# pcb.net
KiCad netlist of a schematic drawn in EAGLE
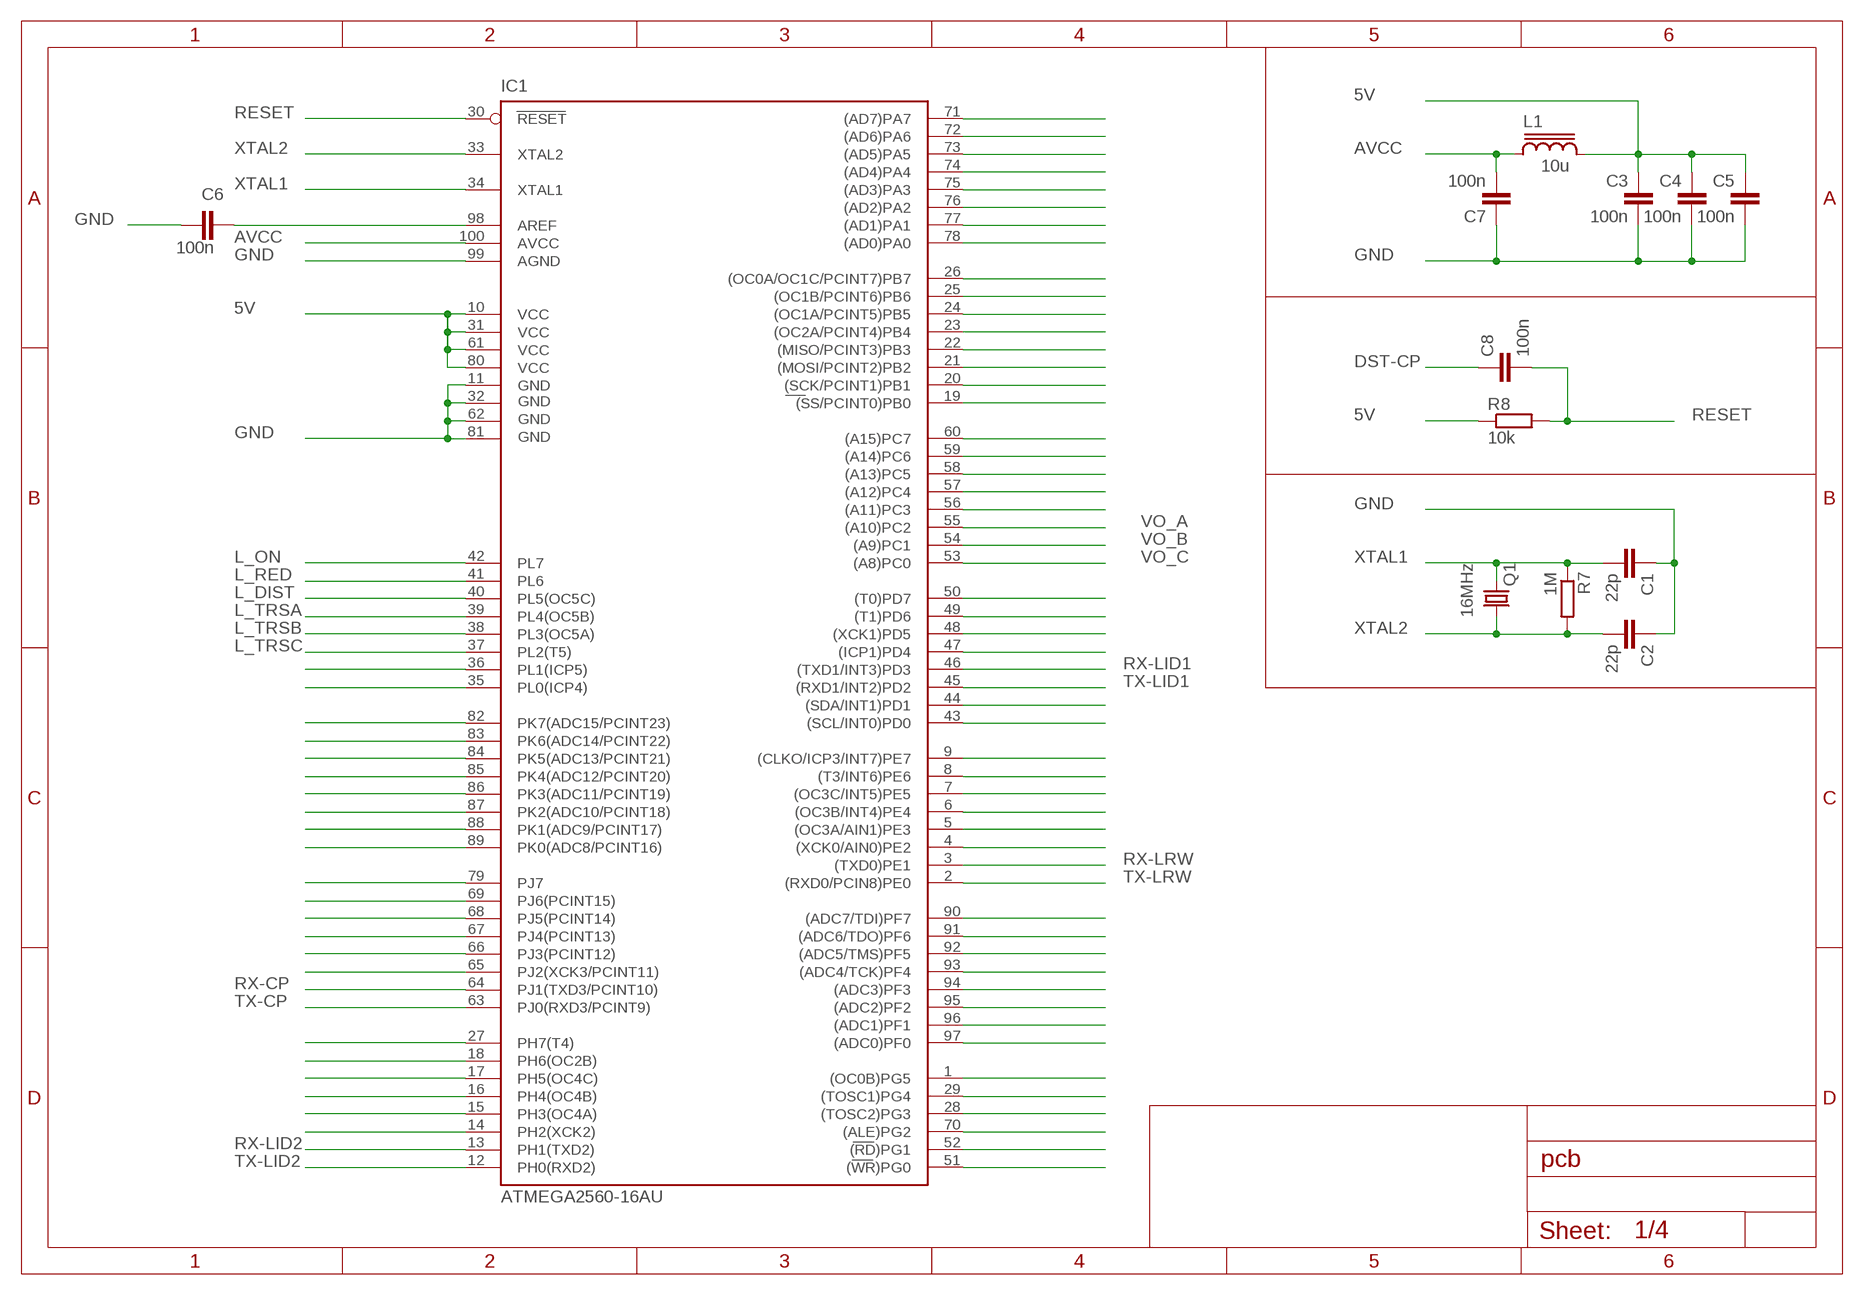
[diagram p0: schematic, sheet 1]
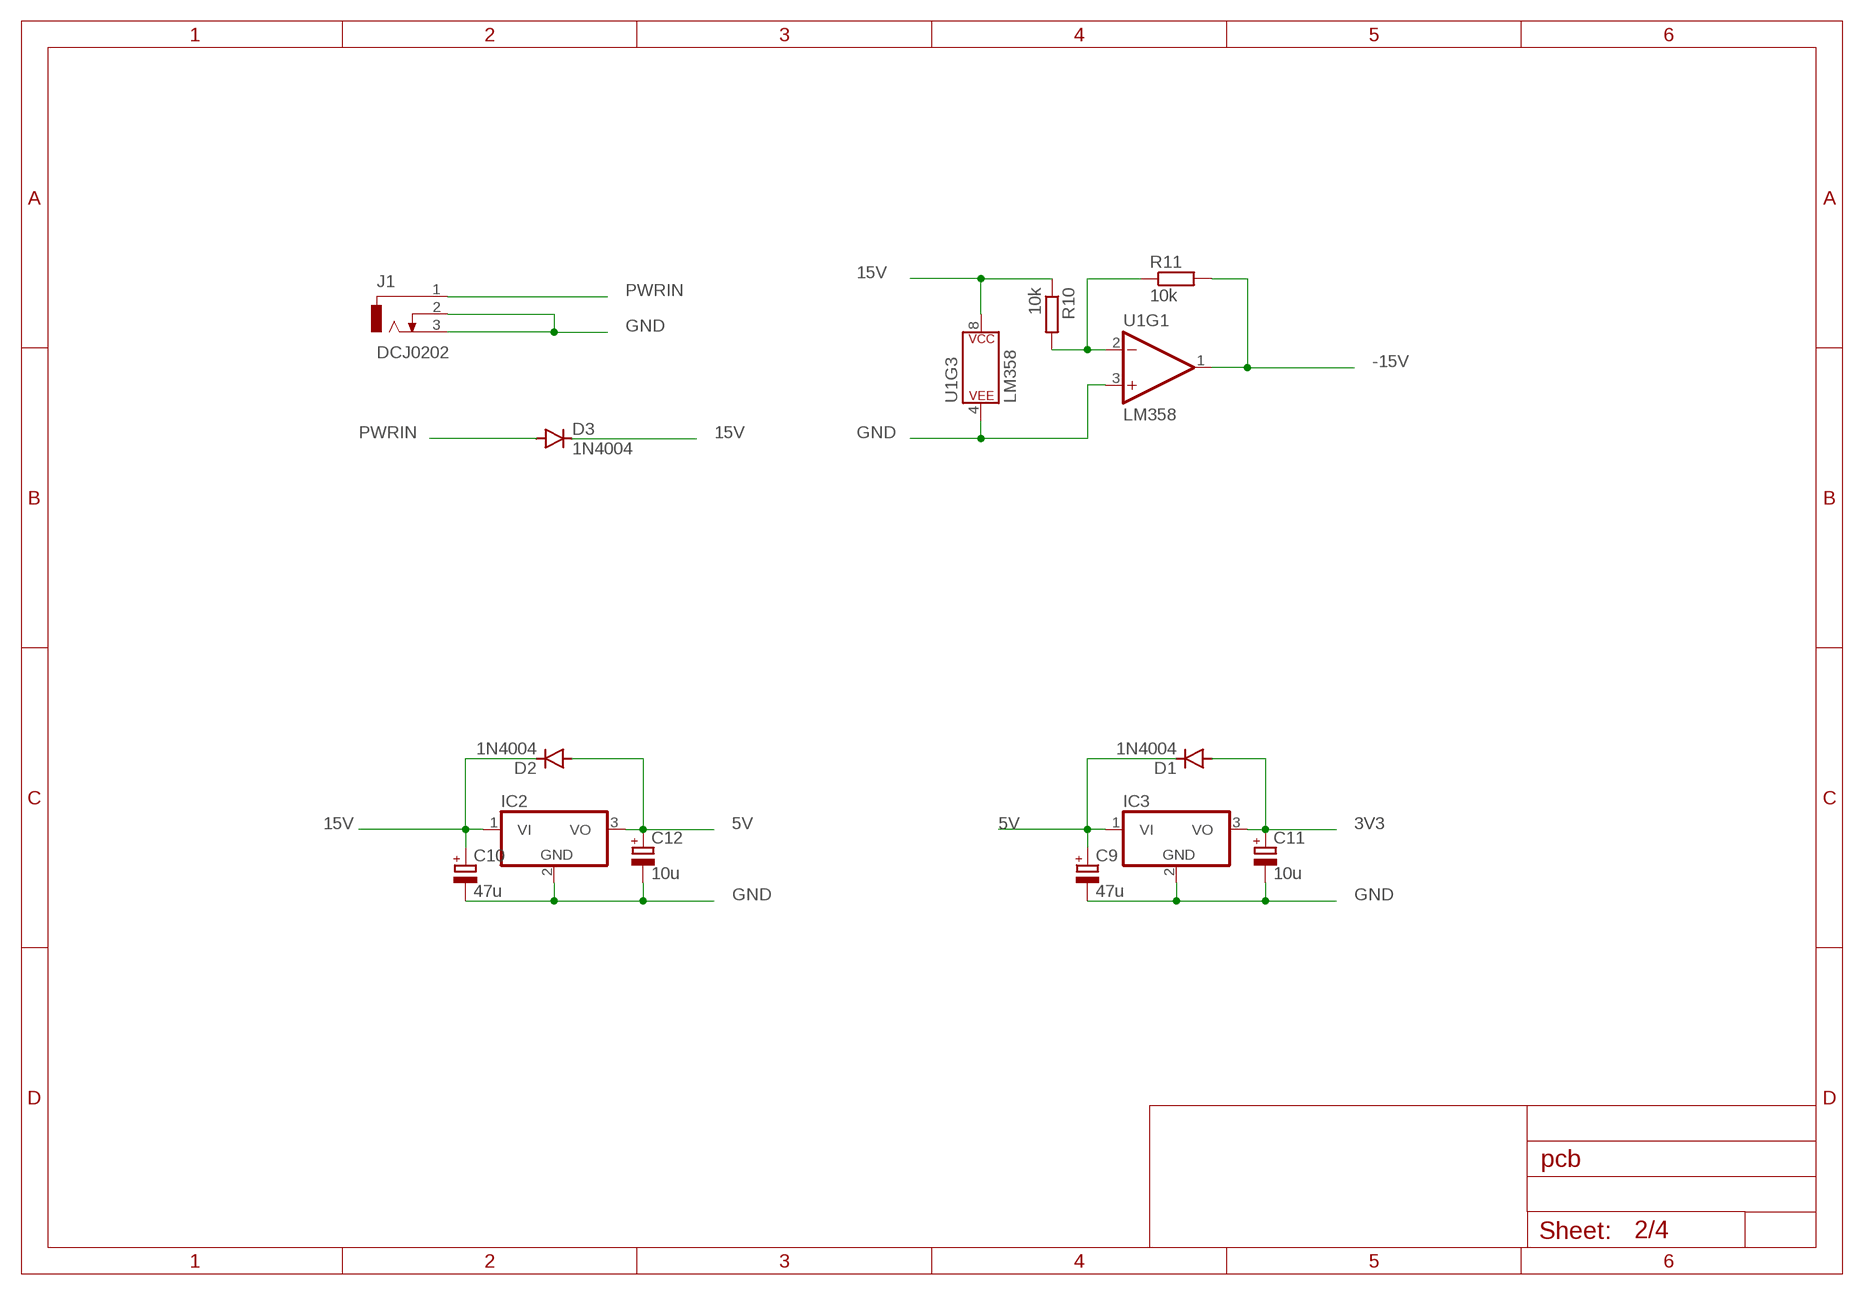
[diagram p1: schematic, sheet 2]
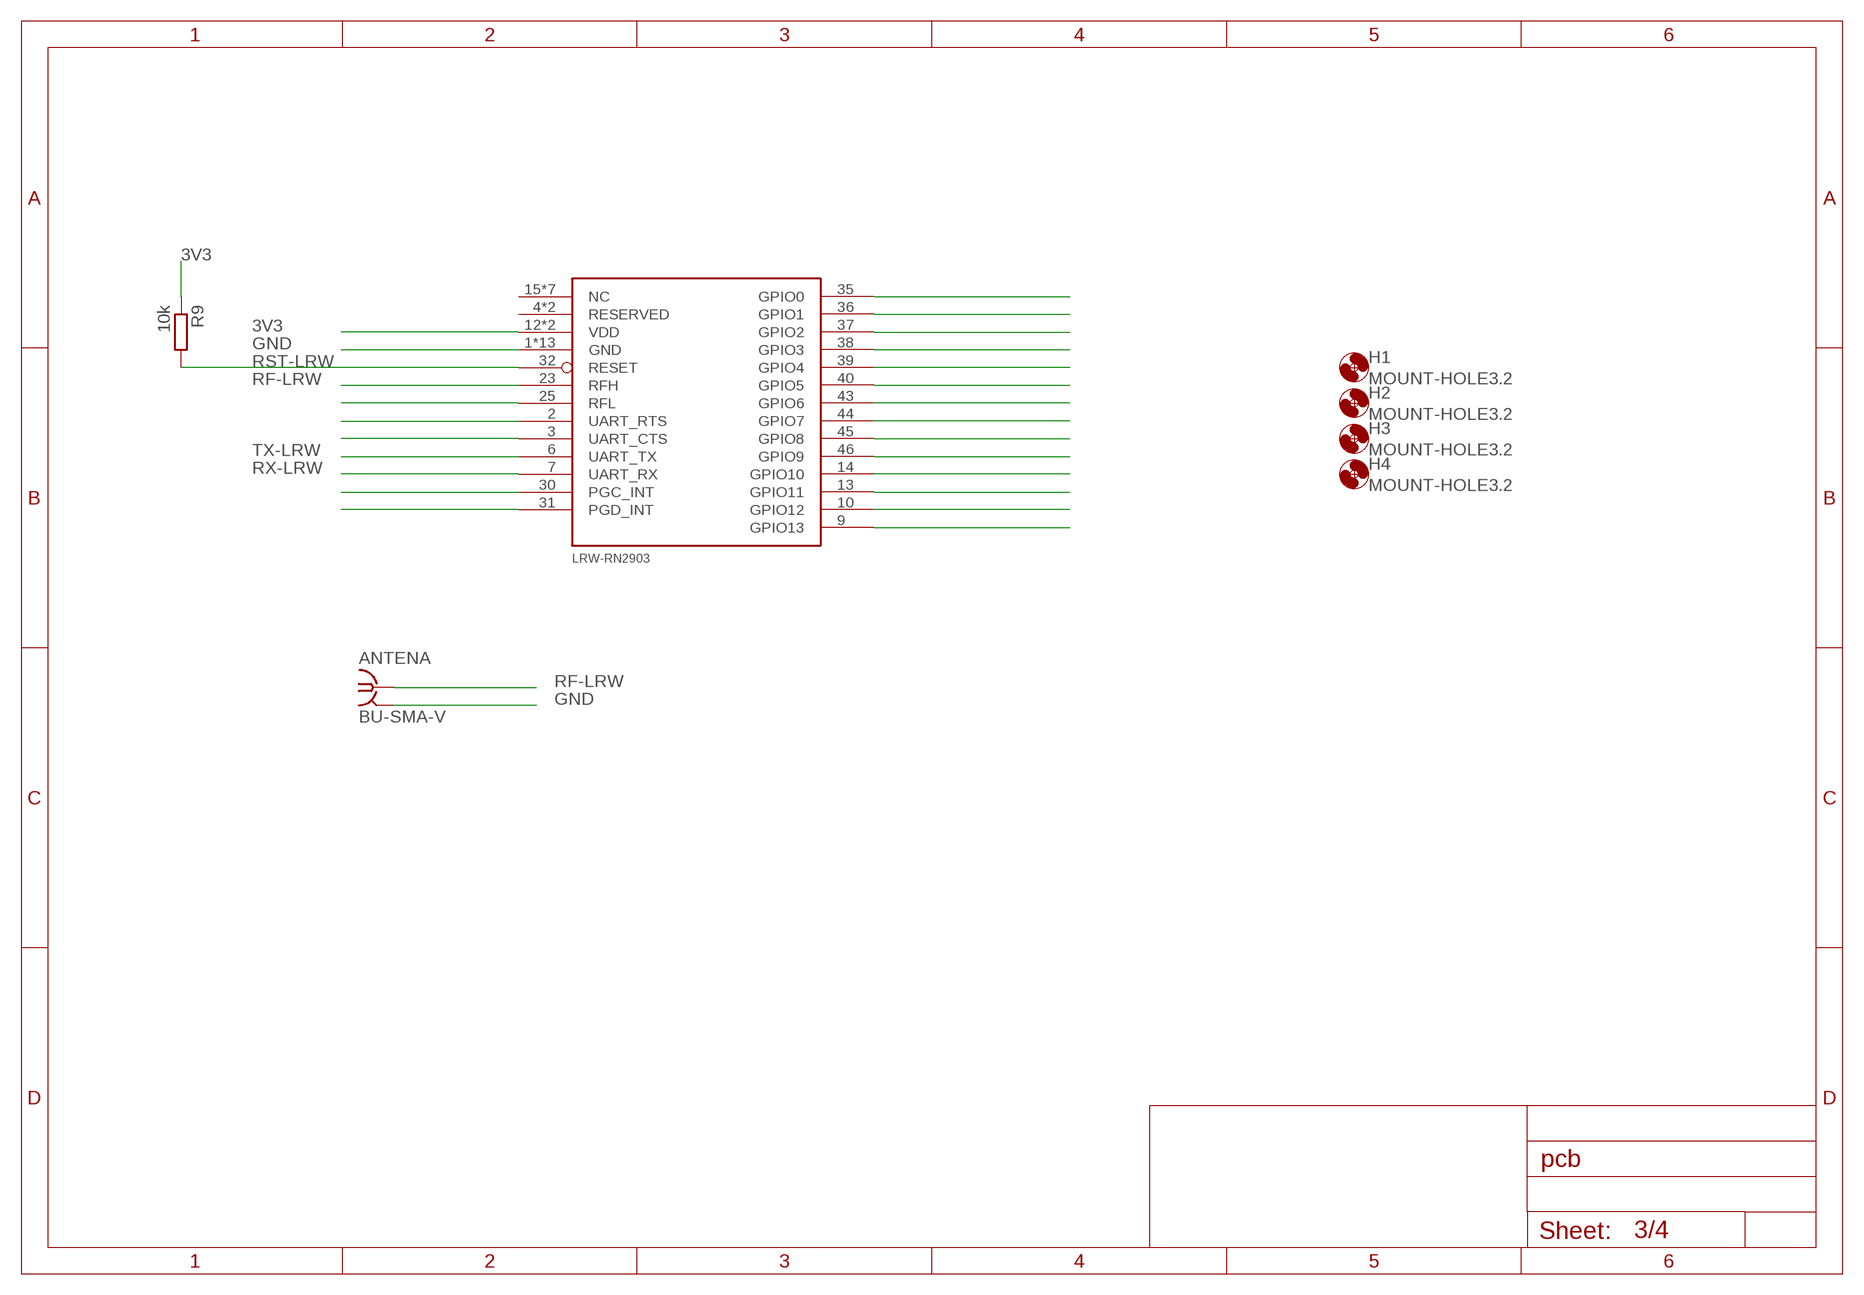
[diagram p2: schematic, sheet 3]
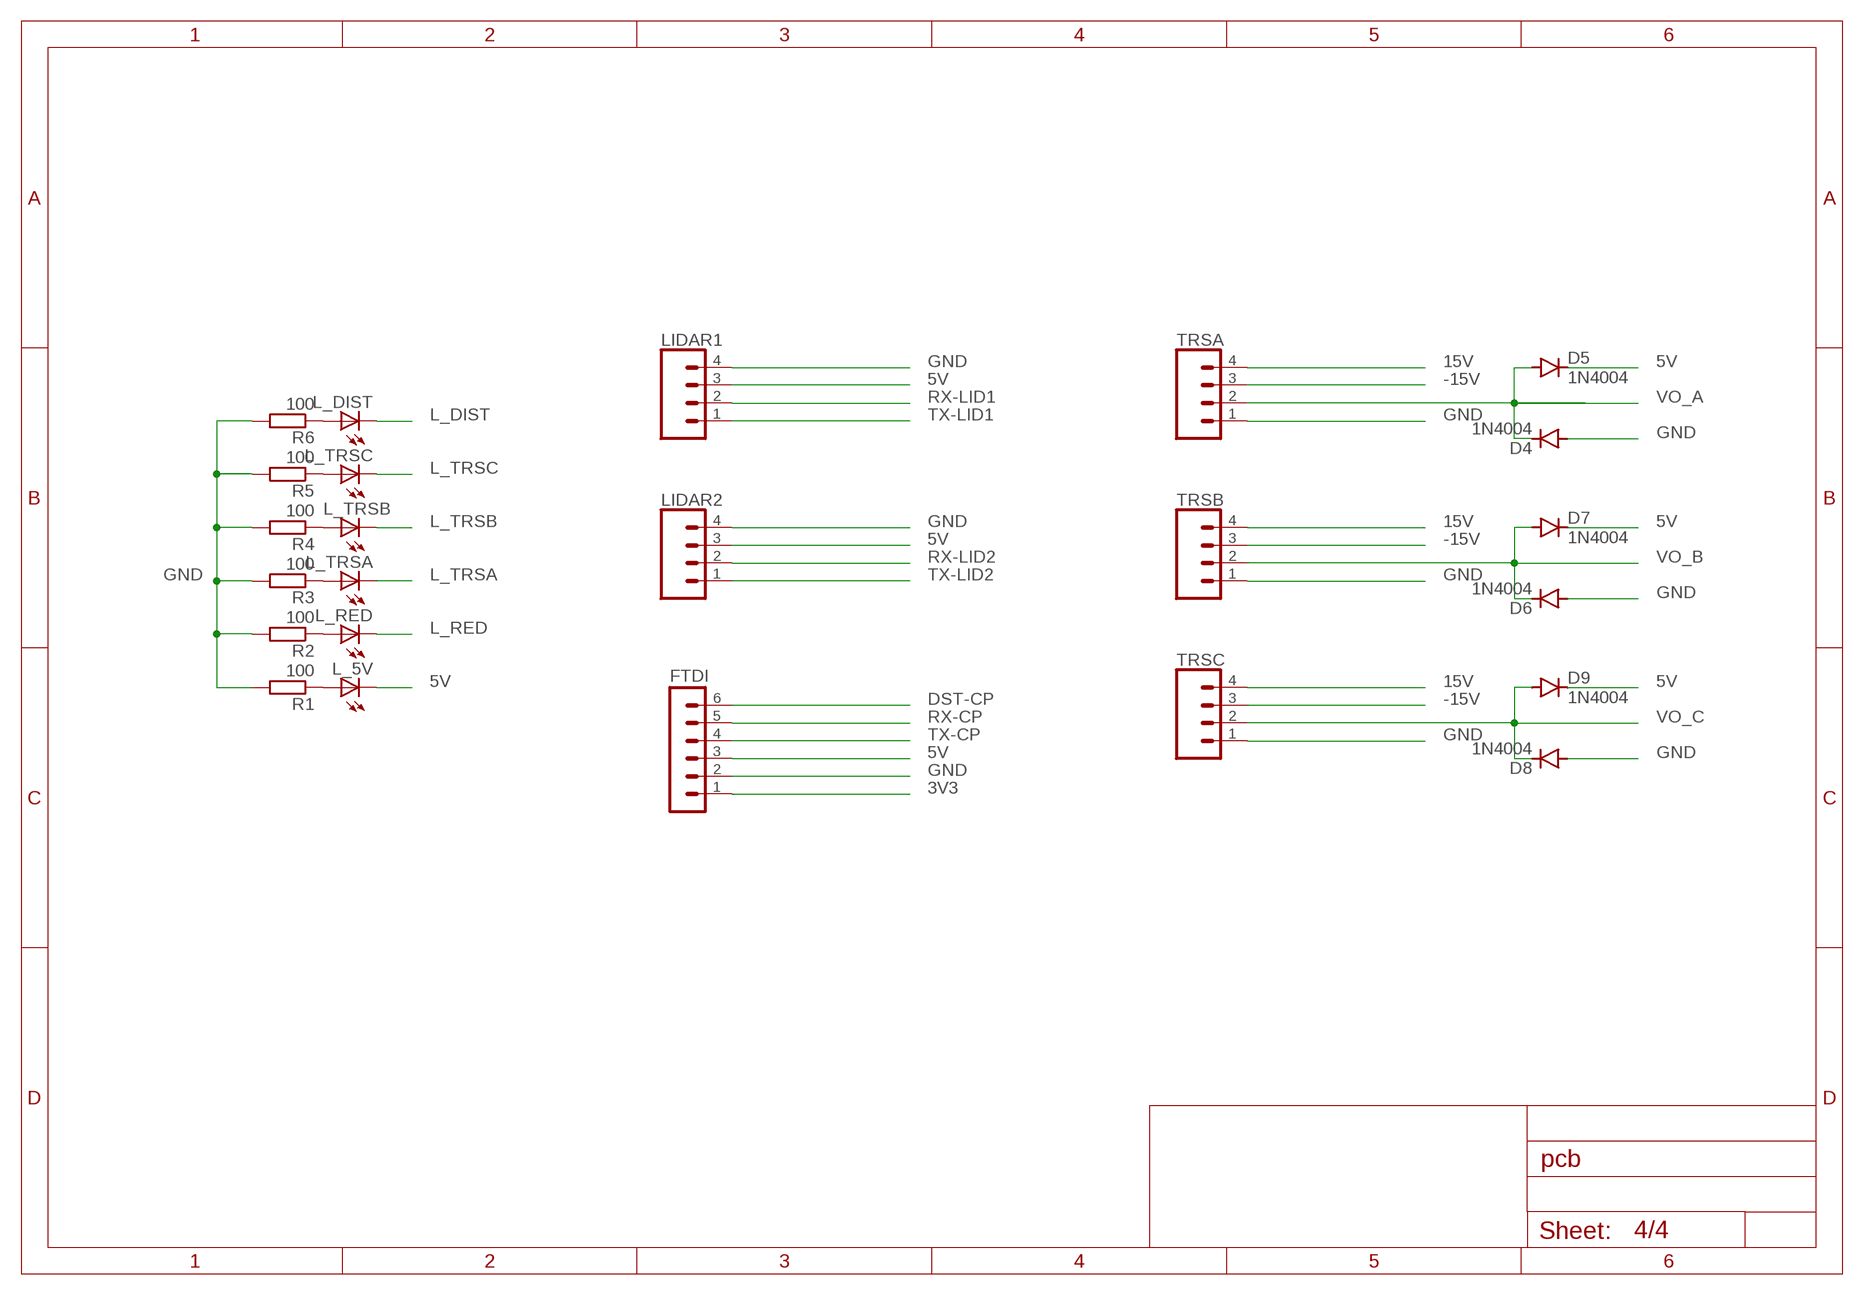
[diagram p3: schematic, sheet 4]

(export (version "E")
  (design (tool "Eeschema 10.0.6"))
  (components
    (comp (ref "C9")
      (value "47u")
      (footprint "eagle-import:E2,5-6E")
      (libsource (lib "eagle-import") (part "CPOL-EUE2,5-6E"))
    )
    (comp (ref "C10")
      (value "47u")
      (footprint "eagle-import:E2,5-6E")
      (libsource (lib "eagle-import") (part "CPOL-EUE2,5-6E"))
    )
    (comp (ref "C11")
      (value "10u")
      (footprint "eagle-import:E2,5-6E")
      (libsource (lib "eagle-import") (part "CPOL-EUE2,5-6E"))
    )
    (comp (ref "C12")
      (value "10u")
      (footprint "eagle-import:E2,5-6E")
      (libsource (lib "eagle-import") (part "CPOL-EUE2,5-6E"))
    )
    (comp (ref "D1")
      (value "1N4004")
      (footprint "eagle-import:DO41-10")
      (libsource (lib "eagle-import") (part "1N4004"))
    )
    (comp (ref "D2")
      (value "1N4004")
      (footprint "eagle-import:DO41-10")
      (libsource (lib "eagle-import") (part "1N4004"))
    )
    (comp (ref "D3")
      (value "1N4004")
      (footprint "eagle-import:DO41-10")
      (libsource (lib "eagle-import") (part "1N4004"))
    )
    (comp (ref "IC2")
      (value "7805T")
      (footprint "eagle-import:TO220H")
      (fields (field (name "VOUT") "5V"))
      (libsource (lib "eagle-import") (part "78T05"))
    )
    (comp (ref "IC3")
      (value "7805T")
      (footprint "eagle-import:TO220H")
      (libsource (lib "eagle-import") (part "78T05"))
    )
    (comp (ref "J1")
      (value "DCJ0202")
      (footprint "eagle-import:DCJ0202")
      (libsource (lib "eagle-import") (part "DCJ0202"))
    )
    (comp (ref "R10")
      (value "10k")
      (footprint "eagle-import:R1206W")
      (libsource (lib "eagle-import") (part "R-EU_R1206W"))
    )
    (comp (ref "R11")
      (value "10k")
      (footprint "eagle-import:R1206W")
      (libsource (lib "eagle-import") (part "R-EU_R1206W"))
    )
    (comp (ref "U1")
      (value "LM358")
      (footprint "eagle-import:DIP08")
      (libsource (lib "eagle-import") (part "LM358"))
    )
    (comp (ref "C1")
      (value "22p")
      (footprint "eagle-import:C050-025X075")
      (libsource (lib "eagle-import") (part "C-EU050-025X075"))
    )
    (comp (ref "C2")
      (value "22p")
      (footprint "eagle-import:C050-025X075")
      (libsource (lib "eagle-import") (part "C-EU050-025X075"))
    )
    (comp (ref "C3")
      (value "100n")
      (footprint "eagle-import:C050-025X075")
      (libsource (lib "eagle-import") (part "C-EU050-025X075"))
    )
    (comp (ref "C4")
      (value "100n")
      (footprint "eagle-import:C050-025X075")
      (libsource (lib "eagle-import") (part "C-EU050-025X075"))
    )
    (comp (ref "C5")
      (value "100n")
      (footprint "eagle-import:C050-025X075")
      (libsource (lib "eagle-import") (part "C-EU050-025X075"))
    )
    (comp (ref "C6")
      (value "100n")
      (footprint "eagle-import:C050-025X075")
      (libsource (lib "eagle-import") (part "C-EU050-025X075"))
    )
    (comp (ref "C7")
      (value "100n")
      (footprint "eagle-import:C050-025X075")
      (libsource (lib "eagle-import") (part "C-EU050-025X075"))
    )
    (comp (ref "C8")
      (value "100n")
      (footprint "eagle-import:C050-025X075")
      (libsource (lib "eagle-import") (part "C-EU050-025X075"))
    )
    (comp (ref "IC1")
      (value "ATMEGA2560-16AU")
      (footprint "eagle-import:TQFP100")
      (libsource (lib "eagle-import") (part "ATMEGAAU2560-16"))
    )
    (comp (ref "L1")
      (value "10u")
      (footprint "eagle-import:MSS1260")
      (libsource (lib "eagle-import") (part "MSS1260"))
    )
    (comp (ref "Q1")
      (value "16MHz")
      (footprint "eagle-import:HC18U-V")
      (libsource (lib "eagle-import") (part "CRYSTALHC18U-V"))
    )
    (comp (ref "R7")
      (value "1M")
      (footprint "eagle-import:R1206W")
      (libsource (lib "eagle-import") (part "R-EU_R1206W"))
    )
    (comp (ref "R8")
      (value "10k")
      (footprint "eagle-import:R1206W")
      (libsource (lib "eagle-import") (part "R-EU_R1206W"))
    )
    (comp (ref "D4")
      (value "1N4004")
      (footprint "eagle-import:DO41-10")
      (libsource (lib "eagle-import") (part "1N4004"))
    )
    (comp (ref "D5")
      (value "1N4004")
      (footprint "eagle-import:DO41-10")
      (libsource (lib "eagle-import") (part "1N4004"))
    )
    (comp (ref "D6")
      (value "1N4004")
      (footprint "eagle-import:DO41-10")
      (libsource (lib "eagle-import") (part "1N4004"))
    )
    (comp (ref "D7")
      (value "1N4004")
      (footprint "eagle-import:DO41-10")
      (libsource (lib "eagle-import") (part "1N4004"))
    )
    (comp (ref "D8")
      (value "1N4004")
      (footprint "eagle-import:DO41-10")
      (libsource (lib "eagle-import") (part "1N4004"))
    )
    (comp (ref "D9")
      (value "1N4004")
      (footprint "eagle-import:DO41-10")
      (libsource (lib "eagle-import") (part "1N4004"))
    )
    (comp (ref "FTDI")
      (value "MA06-1")
      (footprint "eagle-import:MA06-1")
      (libsource (lib "eagle-import") (part "MA06-1"))
    )
    (comp (ref "LIDAR1")
      (value "CONN_04JST-PTH")
      (footprint "eagle-import:JST-4-PTH")
      (libsource (lib "eagle-import") (part "CONN_04JST-PTH"))
    )
    (comp (ref "LIDAR2")
      (value "CONN_04JST-PTH")
      (footprint "eagle-import:JST-4-PTH")
      (libsource (lib "eagle-import") (part "CONN_04JST-PTH"))
    )
    (comp (ref "L_5V")
      (value "LED5MM")
      (footprint "eagle-import:LED5MM")
      (libsource (lib "eagle-import") (part "LED5MM"))
    )
    (comp (ref "L_DIST")
      (value "LED5MM")
      (footprint "eagle-import:LED5MM")
      (libsource (lib "eagle-import") (part "LED5MM"))
    )
    (comp (ref "L_RED")
      (value "LED5MM")
      (footprint "eagle-import:LED5MM")
      (libsource (lib "eagle-import") (part "LED5MM"))
    )
    (comp (ref "L_TRSA")
      (value "LED5MM")
      (footprint "eagle-import:LED5MM")
      (libsource (lib "eagle-import") (part "LED5MM"))
    )
    (comp (ref "L_TRSB")
      (value "LED5MM")
      (footprint "eagle-import:LED5MM")
      (libsource (lib "eagle-import") (part "LED5MM"))
    )
    (comp (ref "L_TRSC")
      (value "LED5MM")
      (footprint "eagle-import:LED5MM")
      (libsource (lib "eagle-import") (part "LED5MM"))
    )
    (comp (ref "R1")
      (value "100")
      (footprint "eagle-import:R1206W")
      (libsource (lib "eagle-import") (part "R-EU_R1206W"))
    )
    (comp (ref "R2")
      (value "100")
      (footprint "eagle-import:R1206W")
      (libsource (lib "eagle-import") (part "R-EU_R1206W"))
    )
    (comp (ref "R3")
      (value "100")
      (footprint "eagle-import:R1206W")
      (libsource (lib "eagle-import") (part "R-EU_R1206W"))
    )
    (comp (ref "R4")
      (value "100")
      (footprint "eagle-import:R1206W")
      (libsource (lib "eagle-import") (part "R-EU_R1206W"))
    )
    (comp (ref "R5")
      (value "100")
      (footprint "eagle-import:R1206W")
      (libsource (lib "eagle-import") (part "R-EU_R1206W"))
    )
    (comp (ref "R6")
      (value "100")
      (footprint "eagle-import:R1206W")
      (libsource (lib "eagle-import") (part "R-EU_R1206W"))
    )
    (comp (ref "TRSA")
      (value "CONN_04JST-PTH")
      (footprint "eagle-import:JST-4-PTH")
      (libsource (lib "eagle-import") (part "CONN_04JST-PTH"))
    )
    (comp (ref "TRSB")
      (value "CONN_04JST-PTH")
      (footprint "eagle-import:JST-4-PTH")
      (libsource (lib "eagle-import") (part "CONN_04JST-PTH"))
    )
    (comp (ref "TRSC")
      (value "CONN_04JST-PTH")
      (footprint "eagle-import:JST-4-PTH")
      (libsource (lib "eagle-import") (part "CONN_04JST-PTH"))
    )
    (comp (ref "ANTENA")
      (value "BU-SMA-V")
      (footprint "eagle-import:BU-SMA-V")
      (libsource (lib "eagle-import") (part "BU-SMA-V"))
    )
    (comp (ref "H1")
      (value "MOUNT-HOLE3.2")
      (footprint "eagle-import:3,2")
      (libsource (lib "eagle-import") (part "MOUNT-HOLE3.2"))
    )
    (comp (ref "H2")
      (value "MOUNT-HOLE3.2")
      (footprint "eagle-import:3,2")
      (libsource (lib "eagle-import") (part "MOUNT-HOLE3.2"))
    )
    (comp (ref "H3")
      (value "MOUNT-HOLE3.2")
      (footprint "eagle-import:3,2")
      (libsource (lib "eagle-import") (part "MOUNT-HOLE3.2"))
    )
    (comp (ref "H4")
      (value "MOUNT-HOLE3.2")
      (footprint "eagle-import:3,2")
      (libsource (lib "eagle-import") (part "MOUNT-HOLE3.2"))
    )
    (comp (ref "LRW-RN2903")
      (value "MICROCHIP_RN2483")
      (footprint "eagle-import:MICROCHIP_RN2483")
      (libsource (lib "eagle-import") (part "MICROCHIP_RN2483"))
    )
    (comp (ref "R9")
      (value "10k")
      (footprint "eagle-import:R1206W")
      (libsource (lib "eagle-import") (part "R-EU_R1206W"))
    )
  )
  (nets
    (net (code "1") (name "-15V") (class "Default")
      (node (ref "R11") (pin "2") (pinfunction "2_2") (pintype "passive"))
      (node (ref "TRSA") (pin "3") (pinfunction "3_3") (pintype "passive"))
      (node (ref "TRSB") (pin "3") (pinfunction "3_3") (pintype "passive"))
      (node (ref "TRSC") (pin "3") (pinfunction "3_3") (pintype "passive"))
      (node (ref "U1") (pin "1") (pinfunction "OUT_1") (pintype "output"))
    )
    (net (code "2") (name "3V3") (class "Default")
      (node (ref "C11") (pin "+") (pinfunction "+_+") (pintype "passive"))
      (node (ref "D1") (pin "A") (pinfunction "A_A") (pintype "passive"))
      (node (ref "FTDI") (pin "1") (pinfunction "1_1") (pintype "passive"))
      (node (ref "IC3") (pin "3") (pinfunction "VO_3") (pintype "passive"))
      (node (ref "LRW-RN2903") (pin "12") (pinfunction "VDD_12") (pintype "power_in"))
      (node (ref "LRW-RN2903") (pin "34") (pinfunction "VDD_34") (pintype "power_in"))
      (node (ref "R9") (pin "1") (pinfunction "1_1") (pintype "passive"))
    )
    (net (code "3") (name "5V") (class "Default")
      (node (ref "C12") (pin "+") (pinfunction "+_+") (pintype "passive"))
      (node (ref "C3") (pin "2") (pinfunction "2_2") (pintype "passive"))
      (node (ref "C4") (pin "2") (pinfunction "2_2") (pintype "passive"))
      (node (ref "C5") (pin "2") (pinfunction "2_2") (pintype "passive"))
      (node (ref "C9") (pin "+") (pinfunction "+_+") (pintype "passive"))
      (node (ref "D1") (pin "C") (pinfunction "C_C") (pintype "passive"))
      (node (ref "D2") (pin "A") (pinfunction "A_A") (pintype "passive"))
      (node (ref "D5") (pin "C") (pinfunction "C_C") (pintype "passive"))
      (node (ref "D7") (pin "C") (pinfunction "C_C") (pintype "passive"))
      (node (ref "D9") (pin "C") (pinfunction "C_C") (pintype "passive"))
      (node (ref "FTDI") (pin "3") (pinfunction "3_3") (pintype "passive"))
      (node (ref "IC1") (pin "10") (pinfunction "VCC_10") (pintype "power_in"))
      (node (ref "IC1") (pin "31") (pinfunction "VCC1_31") (pintype "power_in"))
      (node (ref "IC1") (pin "61") (pinfunction "VCC2_61") (pintype "power_in"))
      (node (ref "IC1") (pin "80") (pinfunction "VCC3_80") (pintype "power_in"))
      (node (ref "IC2") (pin "3") (pinfunction "VO_3") (pintype "passive"))
      (node (ref "IC3") (pin "1") (pinfunction "VI_1") (pintype "input"))
      (node (ref "L1") (pin "2") (pinfunction "2_2") (pintype "passive"))
      (node (ref "LIDAR1") (pin "3") (pinfunction "3_3") (pintype "passive"))
      (node (ref "LIDAR2") (pin "3") (pinfunction "3_3") (pintype "passive"))
      (node (ref "L_5V") (pin "K") (pinfunction "C_K") (pintype "passive"))
      (node (ref "R8") (pin "1") (pinfunction "1_1") (pintype "passive"))
    )
    (net (code "4") (name "15V") (class "Default")
      (node (ref "C10") (pin "+") (pinfunction "+_+") (pintype "passive"))
      (node (ref "D2") (pin "C") (pinfunction "C_C") (pintype "passive"))
      (node (ref "D3") (pin "C") (pinfunction "C_C") (pintype "passive"))
      (node (ref "IC2") (pin "1") (pinfunction "VI_1") (pintype "input"))
      (node (ref "R10") (pin "1") (pinfunction "1_1") (pintype "passive"))
      (node (ref "TRSA") (pin "4") (pinfunction "4_4") (pintype "passive"))
      (node (ref "TRSB") (pin "4") (pinfunction "4_4") (pintype "passive"))
      (node (ref "TRSC") (pin "4") (pinfunction "4_4") (pintype "passive"))
      (node (ref "U1") (pin "8") (pinfunction "P$V+_8") (pintype "bidirectional"))
    )
    (net (code "5") (name "AVCC") (class "Default")
      (node (ref "C7") (pin "2") (pinfunction "2_2") (pintype "passive"))
      (node (ref "IC1") (pin "100") (pinfunction "AVCC_100") (pintype "power_in"))
      (node (ref "L1") (pin "1") (pinfunction "1_1") (pintype "passive"))
    )
    (net (code "6") (name "DST-CP") (class "Default")
      (node (ref "C8") (pin "1") (pinfunction "1_1") (pintype "passive"))
      (node (ref "FTDI") (pin "6") (pinfunction "6_6") (pintype "passive"))
    )
    (net (code "7") (name "GND") (class "Default")
      (node (ref "ANTENA") (pin "2") (pinfunction "2_2") (pintype "passive"))
      (node (ref "ANTENA") (pin "3") (pinfunction "2_3") (pintype "passive"))
      (node (ref "ANTENA") (pin "4") (pinfunction "2_4") (pintype "passive"))
      (node (ref "ANTENA") (pin "5") (pinfunction "2_5") (pintype "passive"))
      (node (ref "C1") (pin "1") (pinfunction "1_1") (pintype "passive"))
      (node (ref "C10") (pin "-") (pinfunction "-_-") (pintype "passive"))
      (node (ref "C11") (pin "-") (pinfunction "-_-") (pintype "passive"))
      (node (ref "C12") (pin "-") (pinfunction "-_-") (pintype "passive"))
      (node (ref "C2") (pin "1") (pinfunction "1_1") (pintype "passive"))
      (node (ref "C3") (pin "1") (pinfunction "1_1") (pintype "passive"))
      (node (ref "C4") (pin "1") (pinfunction "1_1") (pintype "passive"))
      (node (ref "C5") (pin "1") (pinfunction "1_1") (pintype "passive"))
      (node (ref "C6") (pin "2") (pinfunction "2_2") (pintype "passive"))
      (node (ref "C7") (pin "1") (pinfunction "1_1") (pintype "passive"))
      (node (ref "C9") (pin "-") (pinfunction "-_-") (pintype "passive"))
      (node (ref "D4") (pin "A") (pinfunction "A_A") (pintype "passive"))
      (node (ref "D6") (pin "A") (pinfunction "A_A") (pintype "passive"))
      (node (ref "D8") (pin "A") (pinfunction "A_A") (pintype "passive"))
      (node (ref "FTDI") (pin "2") (pinfunction "2_2") (pintype "passive"))
      (node (ref "IC1") (pin "11") (pinfunction "GND_11") (pintype "power_in"))
      (node (ref "IC1") (pin "32") (pinfunction "GND1_32") (pintype "power_in"))
      (node (ref "IC1") (pin "62") (pinfunction "GND2_62") (pintype "power_in"))
      (node (ref "IC1") (pin "81") (pinfunction "GND3_81") (pintype "power_in"))
      (node (ref "IC1") (pin "99") (pinfunction "AGND_99") (pintype "power_in"))
      (node (ref "IC2") (pin "2") (pinfunction "GND_2") (pintype "passive"))
      (node (ref "IC3") (pin "2") (pinfunction "GND_2") (pintype "passive"))
      (node (ref "J1") (pin "2") (pinfunction "2_2") (pintype "passive"))
      (node (ref "J1") (pin "3") (pinfunction "3_3") (pintype "passive"))
      (node (ref "LIDAR1") (pin "4") (pinfunction "4_4") (pintype "passive"))
      (node (ref "LIDAR2") (pin "4") (pinfunction "4_4") (pintype "passive"))
      (node (ref "LRW-RN2903") (pin "1") (pinfunction "GND_1") (pintype "power_in"))
      (node (ref "LRW-RN2903") (pin "11") (pinfunction "GND_11") (pintype "power_in"))
      (node (ref "LRW-RN2903") (pin "20") (pinfunction "GND_20") (pintype "power_in"))
      (node (ref "LRW-RN2903") (pin "21") (pinfunction "GND_21") (pintype "power_in"))
      (node (ref "LRW-RN2903") (pin "22") (pinfunction "GND_22") (pintype "power_in"))
      (node (ref "LRW-RN2903") (pin "24") (pinfunction "GND_24") (pintype "power_in"))
      (node (ref "LRW-RN2903") (pin "26") (pinfunction "GND_26") (pintype "power_in"))
      (node (ref "LRW-RN2903") (pin "27") (pinfunction "GND_27") (pintype "power_in"))
      (node (ref "LRW-RN2903") (pin "28") (pinfunction "GND_28") (pintype "power_in"))
      (node (ref "LRW-RN2903") (pin "33") (pinfunction "GND_33") (pintype "power_in"))
      (node (ref "LRW-RN2903") (pin "41") (pinfunction "GND_41") (pintype "power_in"))
      (node (ref "LRW-RN2903") (pin "47") (pinfunction "GND_47") (pintype "power_in"))
      (node (ref "LRW-RN2903") (pin "8") (pinfunction "GND_8") (pintype "power_in"))
      (node (ref "R1") (pin "2") (pinfunction "2_2") (pintype "passive"))
      (node (ref "R2") (pin "2") (pinfunction "2_2") (pintype "passive"))
      (node (ref "R3") (pin "2") (pinfunction "2_2") (pintype "passive"))
      (node (ref "R4") (pin "2") (pinfunction "2_2") (pintype "passive"))
      (node (ref "R5") (pin "2") (pinfunction "2_2") (pintype "passive"))
      (node (ref "R6") (pin "2") (pinfunction "2_2") (pintype "passive"))
      (node (ref "TRSA") (pin "1") (pinfunction "1_1") (pintype "passive"))
      (node (ref "TRSB") (pin "1") (pinfunction "1_1") (pintype "passive"))
      (node (ref "TRSC") (pin "1") (pinfunction "1_1") (pintype "passive"))
      (node (ref "U1") (pin "3") (pinfunction "+IN_3") (pintype "input"))
      (node (ref "U1") (pin "4") (pinfunction "P$V-_4") (pintype "bidirectional"))
    )
    (net (code "8") (name "L_DIST") (class "Default")
      (node (ref "IC1") (pin "40") (pinfunction "PL5(OC5C)_40") (pintype "bidirectional"))
      (node (ref "L_DIST") (pin "K") (pinfunction "C_K") (pintype "passive"))
    )
    (net (code "9") (name "L_ON") (class "Default")
      (node (ref "IC1") (pin "42") (pinfunction "PL7_42") (pintype "bidirectional"))
    )
    (net (code "10") (name "L_RED") (class "Default")
      (node (ref "IC1") (pin "41") (pinfunction "PL6_41") (pintype "bidirectional"))
      (node (ref "L_RED") (pin "K") (pinfunction "C_K") (pintype "passive"))
    )
    (net (code "11") (name "L_TRSA") (class "Default")
      (node (ref "IC1") (pin "39") (pinfunction "PL4(OC5B)_39") (pintype "bidirectional"))
      (node (ref "L_TRSA") (pin "K") (pinfunction "C_K") (pintype "passive"))
    )
    (net (code "12") (name "L_TRSB") (class "Default")
      (node (ref "IC1") (pin "38") (pinfunction "PL3(OC5A)_38") (pintype "bidirectional"))
      (node (ref "L_TRSB") (pin "K") (pinfunction "C_K") (pintype "passive"))
    )
    (net (code "13") (name "L_TRSC") (class "Default")
      (node (ref "IC1") (pin "37") (pinfunction "PL2(T5)_37") (pintype "bidirectional"))
      (node (ref "L_TRSC") (pin "K") (pinfunction "C_K") (pintype "passive"))
    )
    (net (code "14") (name "Net-(IC1-AREF)") (class "Default")
      (node (ref "C6") (pin "1") (pinfunction "1_1") (pintype "passive"))
      (node (ref "IC1") (pin "98") (pinfunction "AREF_98") (pintype "bidirectional"))
    )
    (net (code "15") (name "Net-(L_5V-PadA)") (class "Default")
      (node (ref "L_5V") (pin "A") (pinfunction "A_A") (pintype "passive"))
      (node (ref "R1") (pin "1") (pinfunction "1_1") (pintype "passive"))
    )
    (net (code "16") (name "Net-(L_DIST-PadA)") (class "Default")
      (node (ref "L_DIST") (pin "A") (pinfunction "A_A") (pintype "passive"))
      (node (ref "R6") (pin "1") (pinfunction "1_1") (pintype "passive"))
    )
    (net (code "17") (name "Net-(L_RED-PadA)") (class "Default")
      (node (ref "L_RED") (pin "A") (pinfunction "A_A") (pintype "passive"))
      (node (ref "R2") (pin "1") (pinfunction "1_1") (pintype "passive"))
    )
    (net (code "18") (name "Net-(L_TRSA-PadA)") (class "Default")
      (node (ref "L_TRSA") (pin "A") (pinfunction "A_A") (pintype "passive"))
      (node (ref "R3") (pin "1") (pinfunction "1_1") (pintype "passive"))
    )
    (net (code "19") (name "Net-(L_TRSB-PadA)") (class "Default")
      (node (ref "L_TRSB") (pin "A") (pinfunction "A_A") (pintype "passive"))
      (node (ref "R4") (pin "1") (pinfunction "1_1") (pintype "passive"))
    )
    (net (code "20") (name "Net-(L_TRSC-PadA)") (class "Default")
      (node (ref "L_TRSC") (pin "A") (pinfunction "A_A") (pintype "passive"))
      (node (ref "R5") (pin "1") (pinfunction "1_1") (pintype "passive"))
    )
    (net (code "21") (name "Net-(U1A--IN)") (class "Default")
      (node (ref "R10") (pin "2") (pinfunction "2_2") (pintype "passive"))
      (node (ref "R11") (pin "1") (pinfunction "1_1") (pintype "passive"))
      (node (ref "U1") (pin "2") (pinfunction "-IN_2") (pintype "input"))
    )
    (net (code "22") (name "PWRIN") (class "Default")
      (node (ref "D3") (pin "A") (pinfunction "A_A") (pintype "passive"))
      (node (ref "J1") (pin "1") (pinfunction "1_1") (pintype "passive"))
    )
    (net (code "23") (name "RESET") (class "Default")
      (node (ref "C8") (pin "2") (pinfunction "2_2") (pintype "passive"))
      (node (ref "IC1") (pin "30") (pinfunction "RESET_30") (pintype "input"))
      (node (ref "R8") (pin "2") (pinfunction "2_2") (pintype "passive"))
    )
    (net (code "24") (name "RF-LRW") (class "Default")
      (node (ref "ANTENA") (pin "1") (pinfunction "1_1") (pintype "passive"))
      (node (ref "LRW-RN2903") (pin "23") (pinfunction "RFH_23") (pintype "bidirectional"))
    )
    (net (code "25") (name "RST-LRW") (class "Default")
      (node (ref "LRW-RN2903") (pin "32") (pinfunction "RESET_32") (pintype "input"))
      (node (ref "R9") (pin "2") (pinfunction "2_2") (pintype "passive"))
    )
    (net (code "26") (name "RX-CP") (class "Default")
      (node (ref "FTDI") (pin "5") (pinfunction "5_5") (pintype "passive"))
      (node (ref "IC1") (pin "64") (pinfunction "PJ1(TXD3/PCINT10)_64") (pintype "bidirectional"))
    )
    (net (code "27") (name "RX-LID1") (class "Default")
      (node (ref "IC1") (pin "46") (pinfunction "(TXD1/INT3)PD3_46") (pintype "bidirectional"))
      (node (ref "LIDAR1") (pin "2") (pinfunction "2_2") (pintype "passive"))
    )
    (net (code "28") (name "RX-LID2") (class "Default")
      (node (ref "IC1") (pin "13") (pinfunction "PH1(TXD2)_13") (pintype "bidirectional"))
      (node (ref "LIDAR2") (pin "2") (pinfunction "2_2") (pintype "passive"))
    )
    (net (code "29") (name "RX-LRW") (class "Default")
      (node (ref "IC1") (pin "3") (pinfunction "(TXD0)PE1_3") (pintype "bidirectional"))
      (node (ref "LRW-RN2903") (pin "7") (pinfunction "UART_RX_7") (pintype "input"))
    )
    (net (code "30") (name "TX-CP") (class "Default")
      (node (ref "FTDI") (pin "4") (pinfunction "4_4") (pintype "passive"))
      (node (ref "IC1") (pin "63") (pinfunction "PJ0(RXD3/PCINT9)_63") (pintype "bidirectional"))
    )
    (net (code "31") (name "TX-LID1") (class "Default")
      (node (ref "IC1") (pin "45") (pinfunction "(RXD1/INT2)PD2_45") (pintype "bidirectional"))
      (node (ref "LIDAR1") (pin "1") (pinfunction "1_1") (pintype "passive"))
    )
    (net (code "32") (name "TX-LID2") (class "Default")
      (node (ref "IC1") (pin "12") (pinfunction "PH0(RXD2)_12") (pintype "bidirectional"))
      (node (ref "LIDAR2") (pin "1") (pinfunction "1_1") (pintype "passive"))
    )
    (net (code "33") (name "TX-LRW") (class "Default")
      (node (ref "IC1") (pin "2") (pinfunction "(RXD0/PCIN8)PE0_2") (pintype "bidirectional"))
      (node (ref "LRW-RN2903") (pin "6") (pinfunction "UART_TX_6") (pintype "output"))
    )
    (net (code "34") (name "VO_A") (class "Default")
      (node (ref "D4") (pin "C") (pinfunction "C_C") (pintype "passive"))
      (node (ref "D5") (pin "A") (pinfunction "A_A") (pintype "passive"))
      (node (ref "IC1") (pin "55") (pinfunction "(A10)PC2_55") (pintype "bidirectional"))
      (node (ref "TRSA") (pin "2") (pinfunction "2_2") (pintype "passive"))
    )
    (net (code "35") (name "VO_B") (class "Default")
      (node (ref "D6") (pin "C") (pinfunction "C_C") (pintype "passive"))
      (node (ref "D7") (pin "A") (pinfunction "A_A") (pintype "passive"))
      (node (ref "IC1") (pin "54") (pinfunction "(A9)PC1_54") (pintype "bidirectional"))
      (node (ref "TRSB") (pin "2") (pinfunction "2_2") (pintype "passive"))
    )
    (net (code "36") (name "VO_C") (class "Default")
      (node (ref "D8") (pin "C") (pinfunction "C_C") (pintype "passive"))
      (node (ref "D9") (pin "A") (pinfunction "A_A") (pintype "passive"))
      (node (ref "IC1") (pin "53") (pinfunction "(A8)PC0_53") (pintype "bidirectional"))
      (node (ref "TRSC") (pin "2") (pinfunction "2_2") (pintype "passive"))
    )
    (net (code "37") (name "XTAL1") (class "Default")
      (node (ref "C1") (pin "2") (pinfunction "2_2") (pintype "passive"))
      (node (ref "IC1") (pin "34") (pinfunction "XTAL1_34") (pintype "input"))
      (node (ref "Q1") (pin "1") (pinfunction "1_1") (pintype "passive"))
      (node (ref "R7") (pin "1") (pinfunction "1_1") (pintype "passive"))
    )
    (net (code "38") (name "XTAL2") (class "Default")
      (node (ref "C2") (pin "2") (pinfunction "2_2") (pintype "passive"))
      (node (ref "IC1") (pin "33") (pinfunction "XTAL2_33") (pintype "output"))
      (node (ref "Q1") (pin "2") (pinfunction "2_2") (pintype "passive"))
      (node (ref "R7") (pin "2") (pinfunction "2_2") (pintype "passive"))
    )
    (net (code "39") (name "unconnected-(IC1-(A11)PC3-Pad56)") (class "Default")
      (node (ref "IC1") (pin "56") (pinfunction "(A11)PC3_56") (pintype "bidirectional"))
    )
    (net (code "40") (name "unconnected-(IC1-(A12)PC4-Pad57)") (class "Default")
      (node (ref "IC1") (pin "57") (pinfunction "(A12)PC4_57") (pintype "bidirectional"))
    )
    (net (code "41") (name "unconnected-(IC1-(A13)PC5-Pad58)") (class "Default")
      (node (ref "IC1") (pin "58") (pinfunction "(A13)PC5_58") (pintype "bidirectional"))
    )
    (net (code "42") (name "unconnected-(IC1-(A14)PC6-Pad59)") (class "Default")
      (node (ref "IC1") (pin "59") (pinfunction "(A14)PC6_59") (pintype "bidirectional"))
    )
    (net (code "43") (name "unconnected-(IC1-(A15)PC7-Pad60)") (class "Default")
      (node (ref "IC1") (pin "60") (pinfunction "(A15)PC7_60") (pintype "bidirectional"))
    )
    (net (code "44") (name "unconnected-(IC1-(AD0)PA0-Pad78)") (class "Default")
      (node (ref "IC1") (pin "78") (pinfunction "(AD0)PA0_78") (pintype "bidirectional"))
    )
    (net (code "45") (name "unconnected-(IC1-(AD1)PA1-Pad77)") (class "Default")
      (node (ref "IC1") (pin "77") (pinfunction "(AD1)PA1_77") (pintype "bidirectional"))
    )
    (net (code "46") (name "unconnected-(IC1-(AD2)PA2-Pad76)") (class "Default")
      (node (ref "IC1") (pin "76") (pinfunction "(AD2)PA2_76") (pintype "bidirectional"))
    )
    (net (code "47") (name "unconnected-(IC1-(AD3)PA3-Pad75)") (class "Default")
      (node (ref "IC1") (pin "75") (pinfunction "(AD3)PA3_75") (pintype "bidirectional"))
    )
    (net (code "48") (name "unconnected-(IC1-(AD4)PA4-Pad74)") (class "Default")
      (node (ref "IC1") (pin "74") (pinfunction "(AD4)PA4_74") (pintype "bidirectional"))
    )
    (net (code "49") (name "unconnected-(IC1-(AD5)PA5-Pad73)") (class "Default")
      (node (ref "IC1") (pin "73") (pinfunction "(AD5)PA5_73") (pintype "bidirectional"))
    )
    (net (code "50") (name "unconnected-(IC1-(AD6)PA6-Pad72)") (class "Default")
      (node (ref "IC1") (pin "72") (pinfunction "(AD6)PA6_72") (pintype "bidirectional"))
    )
    (net (code "51") (name "unconnected-(IC1-(AD7)PA7-Pad71)") (class "Default")
      (node (ref "IC1") (pin "71") (pinfunction "(AD7)PA7_71") (pintype "bidirectional"))
    )
    (net (code "52") (name "unconnected-(IC1-(ADC0)PF0-Pad97)") (class "Default")
      (node (ref "IC1") (pin "97") (pinfunction "(ADC0)PF0_97") (pintype "bidirectional"))
    )
    (net (code "53") (name "unconnected-(IC1-(ADC1)PF1-Pad96)") (class "Default")
      (node (ref "IC1") (pin "96") (pinfunction "(ADC1)PF1_96") (pintype "bidirectional"))
    )
    (net (code "54") (name "unconnected-(IC1-(ADC2)PF2-Pad95)") (class "Default")
      (node (ref "IC1") (pin "95") (pinfunction "(ADC2)PF2_95") (pintype "bidirectional"))
    )
    (net (code "55") (name "unconnected-(IC1-(ADC3)PF3-Pad94)") (class "Default")
      (node (ref "IC1") (pin "94") (pinfunction "(ADC3)PF3_94") (pintype "bidirectional"))
    )
    (net (code "56") (name "unconnected-(IC1-(ADC4{slash}TCK)PF4-Pad93)") (class "Default")
      (node (ref "IC1") (pin "93") (pinfunction "(ADC4/TCK)PF4_93") (pintype "bidirectional"))
    )
    (net (code "57") (name "unconnected-(IC1-(ADC5{slash}TMS)PF5-Pad92)") (class "Default")
      (node (ref "IC1") (pin "92") (pinfunction "(ADC5/TMS)PF5_92") (pintype "bidirectional"))
    )
    (net (code "58") (name "unconnected-(IC1-(ADC6{slash}TDO)PF6-Pad91)") (class "Default")
      (node (ref "IC1") (pin "91") (pinfunction "(ADC6/TDO)PF6_91") (pintype "bidirectional"))
    )
    (net (code "59") (name "unconnected-(IC1-(ADC7{slash}TDI)PF7-Pad90)") (class "Default")
      (node (ref "IC1") (pin "90") (pinfunction "(ADC7/TDI)PF7_90") (pintype "bidirectional"))
    )
    (net (code "60") (name "unconnected-(IC1-(ALE)PG2-Pad70)") (class "Default")
      (node (ref "IC1") (pin "70") (pinfunction "(ALE)PG2_70") (pintype "bidirectional"))
    )
    (net (code "61") (name "unconnected-(IC1-(CLKO{slash}ICP3{slash}INT7)PE7-Pad9)") (class "Default")
      (node (ref "IC1") (pin "9") (pinfunction "(CLKO/ICP3/INT7)PE7_9") (pintype "bidirectional"))
    )
    (net (code "62") (name "unconnected-(IC1-(ICP1)PD4-Pad47)") (class "Default")
      (node (ref "IC1") (pin "47") (pinfunction "(ICP1)PD4_47") (pintype "bidirectional"))
    )
    (net (code "63") (name "unconnected-(IC1-(MISO{slash}PCINT3)PB3-Pad22)") (class "Default")
      (node (ref "IC1") (pin "22") (pinfunction "(MISO/PCINT3)PB3_22") (pintype "bidirectional"))
    )
    (net (code "64") (name "unconnected-(IC1-(MOSI{slash}PCINT2)PB2-Pad21)") (class "Default")
      (node (ref "IC1") (pin "21") (pinfunction "(MOSI/PCINT2)PB2_21") (pintype "bidirectional"))
    )
    (net (code "65") (name "unconnected-(IC1-(OC0A{slash}OC1C{slash}PCINT7)PB7-Pad26)") (class "Default")
      (node (ref "IC1") (pin "26") (pinfunction "(OC0A/OC1C/PCINT7)PB7_26") (pintype "bidirectional"))
    )
    (net (code "66") (name "unconnected-(IC1-(OC0B)PG5-Pad1)") (class "Default")
      (node (ref "IC1") (pin "1") (pinfunction "(OC0B)PG5_1") (pintype "bidirectional"))
    )
    (net (code "67") (name "unconnected-(IC1-(OC1A{slash}PCINT5)PB5-Pad24)") (class "Default")
      (node (ref "IC1") (pin "24") (pinfunction "(OC1A/PCINT5)PB5_24") (pintype "bidirectional"))
    )
    (net (code "68") (name "unconnected-(IC1-(OC1B{slash}PCINT6)PB6-Pad25)") (class "Default")
      (node (ref "IC1") (pin "25") (pinfunction "(OC1B/PCINT6)PB6_25") (pintype "bidirectional"))
    )
    (net (code "69") (name "unconnected-(IC1-(OC2A{slash}PCINT4)PB4-Pad23)") (class "Default")
      (node (ref "IC1") (pin "23") (pinfunction "(OC2A/PCINT4)PB4_23") (pintype "bidirectional"))
    )
    (net (code "70") (name "unconnected-(IC1-(OC3A{slash}AIN1)PE3-Pad5)") (class "Default")
      (node (ref "IC1") (pin "5") (pinfunction "(OC3A/AIN1)PE3_5") (pintype "bidirectional"))
    )
    (net (code "71") (name "unconnected-(IC1-(OC3B{slash}INT4)PE4-Pad6)") (class "Default")
      (node (ref "IC1") (pin "6") (pinfunction "(OC3B/INT4)PE4_6") (pintype "bidirectional"))
    )
    (net (code "72") (name "unconnected-(IC1-(OC3C{slash}INT5)PE5-Pad7)") (class "Default")
      (node (ref "IC1") (pin "7") (pinfunction "(OC3C/INT5)PE5_7") (pintype "bidirectional"))
    )
    (net (code "73") (name "unconnected-(IC1-(RD)PG1-Pad52)") (class "Default")
      (node (ref "IC1") (pin "52") (pinfunction "(RD)PG1_52") (pintype "bidirectional"))
    )
    (net (code "74") (name "unconnected-(IC1-(SCK{slash}PCINT1)PB1-Pad20)") (class "Default")
      (node (ref "IC1") (pin "20") (pinfunction "(SCK/PCINT1)PB1_20") (pintype "bidirectional"))
    )
    (net (code "75") (name "unconnected-(IC1-(SCL{slash}INT0)PD0-Pad43)") (class "Default")
      (node (ref "IC1") (pin "43") (pinfunction "(SCL/INT0)PD0_43") (pintype "bidirectional"))
    )
    (net (code "76") (name "unconnected-(IC1-(SDA{slash}INT1)PD1-Pad44)") (class "Default")
      (node (ref "IC1") (pin "44") (pinfunction "(SDA/INT1)PD1_44") (pintype "bidirectional"))
    )
    (net (code "77") (name "unconnected-(IC1-(SS{slash}PCINT0)PB0-Pad19)") (class "Default")
      (node (ref "IC1") (pin "19") (pinfunction "(SS/PCINT0)PB0_19") (pintype "bidirectional"))
    )
    (net (code "78") (name "unconnected-(IC1-(T0)PD7-Pad50)") (class "Default")
      (node (ref "IC1") (pin "50") (pinfunction "(T0)PD7_50") (pintype "bidirectional"))
    )
    (net (code "79") (name "unconnected-(IC1-(T1)PD6-Pad49)") (class "Default")
      (node (ref "IC1") (pin "49") (pinfunction "(T1)PD6_49") (pintype "bidirectional"))
    )
    (net (code "80") (name "unconnected-(IC1-(T3{slash}INT6)PE6-Pad8)") (class "Default")
      (node (ref "IC1") (pin "8") (pinfunction "(T3/INT6)PE6_8") (pintype "bidirectional"))
    )
    (net (code "81") (name "unconnected-(IC1-(TOSC1)PG4-Pad29)") (class "Default")
      (node (ref "IC1") (pin "29") (pinfunction "(TOSC1)PG4_29") (pintype "bidirectional"))
    )
    (net (code "82") (name "unconnected-(IC1-(TOSC2)PG3-Pad28)") (class "Default")
      (node (ref "IC1") (pin "28") (pinfunction "(TOSC2)PG3_28") (pintype "bidirectional"))
    )
    (net (code "83") (name "unconnected-(IC1-(WR)PG0-Pad51)") (class "Default")
      (node (ref "IC1") (pin "51") (pinfunction "(WR)PG0_51") (pintype "bidirectional"))
    )
    (net (code "84") (name "unconnected-(IC1-(XCK0{slash}AIN0)PE2-Pad4)") (class "Default")
      (node (ref "IC1") (pin "4") (pinfunction "(XCK0/AIN0)PE2_4") (pintype "bidirectional"))
    )
    (net (code "85") (name "unconnected-(IC1-(XCK1)PD5-Pad48)") (class "Default")
      (node (ref "IC1") (pin "48") (pinfunction "(XCK1)PD5_48") (pintype "bidirectional"))
    )
    (net (code "86") (name "unconnected-(IC1-PH2(XCK2)-Pad14)") (class "Default")
      (node (ref "IC1") (pin "14") (pinfunction "PH2(XCK2)_14") (pintype "bidirectional"))
    )
    (net (code "87") (name "unconnected-(IC1-PH3(OC4A)-Pad15)") (class "Default")
      (node (ref "IC1") (pin "15") (pinfunction "PH3(OC4A)_15") (pintype "bidirectional"))
    )
    (net (code "88") (name "unconnected-(IC1-PH4(OC4B)-Pad16)") (class "Default")
      (node (ref "IC1") (pin "16") (pinfunction "PH4(OC4B)_16") (pintype "bidirectional"))
    )
    (net (code "89") (name "unconnected-(IC1-PH5(OC4C)-Pad17)") (class "Default")
      (node (ref "IC1") (pin "17") (pinfunction "PH5(OC4C)_17") (pintype "bidirectional"))
    )
    (net (code "90") (name "unconnected-(IC1-PH6(OC2B)-Pad18)") (class "Default")
      (node (ref "IC1") (pin "18") (pinfunction "PH6(OC2B)_18") (pintype "bidirectional"))
    )
    (net (code "91") (name "unconnected-(IC1-PH7(T4)-Pad27)") (class "Default")
      (node (ref "IC1") (pin "27") (pinfunction "PH7(T4)_27") (pintype "bidirectional"))
    )
    (net (code "92") (name "unconnected-(IC1-PJ2(XCK3{slash}PCINT11)-Pad65)") (class "Default")
      (node (ref "IC1") (pin "65") (pinfunction "PJ2(XCK3/PCINT11)_65") (pintype "bidirectional"))
    )
    (net (code "93") (name "unconnected-(IC1-PJ3(PCINT12)-Pad66)") (class "Default")
      (node (ref "IC1") (pin "66") (pinfunction "PJ3(PCINT12)_66") (pintype "bidirectional"))
    )
    (net (code "94") (name "unconnected-(IC1-PJ4(PCINT13)-Pad67)") (class "Default")
      (node (ref "IC1") (pin "67") (pinfunction "PJ4(PCINT13)_67") (pintype "bidirectional"))
    )
    (net (code "95") (name "unconnected-(IC1-PJ5(PCINT14)-Pad68)") (class "Default")
      (node (ref "IC1") (pin "68") (pinfunction "PJ5(PCINT14)_68") (pintype "bidirectional"))
    )
    (net (code "96") (name "unconnected-(IC1-PJ6(PCINT15)-Pad69)") (class "Default")
      (node (ref "IC1") (pin "69") (pinfunction "PJ6(PCINT15)_69") (pintype "bidirectional"))
    )
    (net (code "97") (name "unconnected-(IC1-PJ7-Pad79)") (class "Default")
      (node (ref "IC1") (pin "79") (pinfunction "PJ7_79") (pintype "bidirectional"))
    )
    (net (code "98") (name "unconnected-(IC1-PK0(ADC8{slash}PCINT16)-Pad89)") (class "Default")
      (node (ref "IC1") (pin "89") (pinfunction "PK0(ADC8/PCINT16)_89") (pintype "bidirectional"))
    )
    (net (code "99") (name "unconnected-(IC1-PK1(ADC9{slash}PCINT17)-Pad88)") (class "Default")
      (node (ref "IC1") (pin "88") (pinfunction "PK1(ADC9/PCINT17)_88") (pintype "bidirectional"))
    )
    (net (code "100") (name "unconnected-(IC1-PK2(ADC10{slash}PCINT18)-Pad87)") (class "Default")
      (node (ref "IC1") (pin "87") (pinfunction "PK2(ADC10/PCINT18)_87") (pintype "bidirectional"))
    )
    (net (code "101") (name "unconnected-(IC1-PK3(ADC11{slash}PCINT19)-Pad86)") (class "Default")
      (node (ref "IC1") (pin "86") (pinfunction "PK3(ADC11/PCINT19)_86") (pintype "bidirectional"))
    )
    (net (code "102") (name "unconnected-(IC1-PK4(ADC12{slash}PCINT20)-Pad85)") (class "Default")
      (node (ref "IC1") (pin "85") (pinfunction "PK4(ADC12/PCINT20)_85") (pintype "bidirectional"))
    )
    (net (code "103") (name "unconnected-(IC1-PK5(ADC13{slash}PCINT21)-Pad84)") (class "Default")
      (node (ref "IC1") (pin "84") (pinfunction "PK5(ADC13/PCINT21)_84") (pintype "bidirectional"))
    )
    (net (code "104") (name "unconnected-(IC1-PK6(ADC14{slash}PCINT22)-Pad83)") (class "Default")
      (node (ref "IC1") (pin "83") (pinfunction "PK6(ADC14/PCINT22)_83") (pintype "bidirectional"))
    )
    (net (code "105") (name "unconnected-(IC1-PK7(ADC15{slash}PCINT23)-Pad82)") (class "Default")
      (node (ref "IC1") (pin "82") (pinfunction "PK7(ADC15/PCINT23)_82") (pintype "bidirectional"))
    )
    (net (code "106") (name "unconnected-(IC1-PL0(ICP4)-Pad35)") (class "Default")
      (node (ref "IC1") (pin "35") (pinfunction "PL0(ICP4)_35") (pintype "bidirectional"))
    )
    (net (code "107") (name "unconnected-(IC1-PL1(ICP5)-Pad36)") (class "Default")
      (node (ref "IC1") (pin "36") (pinfunction "PL1(ICP5)_36") (pintype "bidirectional"))
    )
    (net (code "108") (name "unconnected-(LRW-RN2903-GPIO0-Pad35)") (class "Default")
      (node (ref "LRW-RN2903") (pin "35") (pinfunction "GPIO0_35") (pintype "bidirectional"))
    )
    (net (code "109") (name "unconnected-(LRW-RN2903-GPIO1-Pad36)") (class "Default")
      (node (ref "LRW-RN2903") (pin "36") (pinfunction "GPIO1_36") (pintype "bidirectional"))
    )
    (net (code "110") (name "unconnected-(LRW-RN2903-GPIO2-Pad37)") (class "Default")
      (node (ref "LRW-RN2903") (pin "37") (pinfunction "GPIO2_37") (pintype "bidirectional"))
    )
    (net (code "111") (name "unconnected-(LRW-RN2903-GPIO3-Pad38)") (class "Default")
      (node (ref "LRW-RN2903") (pin "38") (pinfunction "GPIO3_38") (pintype "bidirectional"))
    )
    (net (code "112") (name "unconnected-(LRW-RN2903-GPIO4-Pad39)") (class "Default")
      (node (ref "LRW-RN2903") (pin "39") (pinfunction "GPIO4_39") (pintype "bidirectional"))
    )
    (net (code "113") (name "unconnected-(LRW-RN2903-GPIO5-Pad40)") (class "Default")
      (node (ref "LRW-RN2903") (pin "40") (pinfunction "GPIO5_40") (pintype "bidirectional"))
    )
    (net (code "114") (name "unconnected-(LRW-RN2903-GPIO6-Pad43)") (class "Default")
      (node (ref "LRW-RN2903") (pin "43") (pinfunction "GPIO6_43") (pintype "bidirectional"))
    )
    (net (code "115") (name "unconnected-(LRW-RN2903-GPIO7-Pad44)") (class "Default")
      (node (ref "LRW-RN2903") (pin "44") (pinfunction "GPIO7_44") (pintype "bidirectional"))
    )
    (net (code "116") (name "unconnected-(LRW-RN2903-GPIO8-Pad45)") (class "Default")
      (node (ref "LRW-RN2903") (pin "45") (pinfunction "GPIO8_45") (pintype "bidirectional"))
    )
    (net (code "117") (name "unconnected-(LRW-RN2903-GPIO9-Pad46)") (class "Default")
      (node (ref "LRW-RN2903") (pin "46") (pinfunction "GPIO9_46") (pintype "bidirectional"))
    )
    (net (code "118") (name "unconnected-(LRW-RN2903-GPIO10-Pad14)") (class "Default")
      (node (ref "LRW-RN2903") (pin "14") (pinfunction "GPIO10_14") (pintype "bidirectional"))
    )
    (net (code "119") (name "unconnected-(LRW-RN2903-GPIO11-Pad13)") (class "Default")
      (node (ref "LRW-RN2903") (pin "13") (pinfunction "GPIO11_13") (pintype "bidirectional"))
    )
    (net (code "120") (name "unconnected-(LRW-RN2903-GPIO12-Pad10)") (class "Default")
      (node (ref "LRW-RN2903") (pin "10") (pinfunction "GPIO12_10") (pintype "bidirectional"))
    )
    (net (code "121") (name "unconnected-(LRW-RN2903-GPIO13-Pad9)") (class "Default")
      (node (ref "LRW-RN2903") (pin "9") (pinfunction "GPIO13_9") (pintype "bidirectional"))
    )
    (net (code "122") (name "unconnected-(LRW-RN2903-NC-Pad15)") (class "Default")
      (node (ref "LRW-RN2903") (pin "15") (pinfunction "NC_15") (pintype "no_connect"))
    )
    (net (code "123") (name "unconnected-(LRW-RN2903-NC-Pad16)") (class "Default")
      (node (ref "LRW-RN2903") (pin "16") (pinfunction "NC_16") (pintype "no_connect"))
    )
    (net (code "124") (name "unconnected-(LRW-RN2903-NC-Pad17)") (class "Default")
      (node (ref "LRW-RN2903") (pin "17") (pinfunction "NC_17") (pintype "no_connect"))
    )
    (net (code "125") (name "unconnected-(LRW-RN2903-NC-Pad18)") (class "Default")
      (node (ref "LRW-RN2903") (pin "18") (pinfunction "NC_18") (pintype "no_connect"))
    )
    (net (code "126") (name "unconnected-(LRW-RN2903-NC-Pad19)") (class "Default")
      (node (ref "LRW-RN2903") (pin "19") (pinfunction "NC_19") (pintype "no_connect"))
    )
    (net (code "127") (name "unconnected-(LRW-RN2903-NC-Pad29)") (class "Default")
      (node (ref "LRW-RN2903") (pin "29") (pinfunction "NC_29") (pintype "no_connect"))
    )
    (net (code "128") (name "unconnected-(LRW-RN2903-NC-Pad42)") (class "Default")
      (node (ref "LRW-RN2903") (pin "42") (pinfunction "NC_42") (pintype "no_connect"))
    )
    (net (code "129") (name "unconnected-(LRW-RN2903-PGC_INT-Pad30)") (class "Default")
      (node (ref "LRW-RN2903") (pin "30") (pinfunction "PGC_INT_30") (pintype "bidirectional"))
    )
    (net (code "130") (name "unconnected-(LRW-RN2903-PGD_INT-Pad31)") (class "Default")
      (node (ref "LRW-RN2903") (pin "31") (pinfunction "PGD_INT_31") (pintype "bidirectional"))
    )
    (net (code "131") (name "unconnected-(LRW-RN2903-RESERVED-Pad4)") (class "Default")
      (node (ref "LRW-RN2903") (pin "4") (pinfunction "RESERVED_4") (pintype "no_connect"))
    )
    (net (code "132") (name "unconnected-(LRW-RN2903-RESERVED-Pad5)") (class "Default")
      (node (ref "LRW-RN2903") (pin "5") (pinfunction "RESERVED_5") (pintype "no_connect"))
    )
    (net (code "133") (name "unconnected-(LRW-RN2903-RFL-Pad25)") (class "Default")
      (node (ref "LRW-RN2903") (pin "25") (pinfunction "RFL_25") (pintype "bidirectional"))
    )
    (net (code "134") (name "unconnected-(LRW-RN2903-UART_CTS-Pad3)") (class "Default")
      (node (ref "LRW-RN2903") (pin "3") (pinfunction "UART_CTS_3") (pintype "input"))
    )
    (net (code "135") (name "unconnected-(LRW-RN2903-UART_RTS-Pad2)") (class "Default")
      (node (ref "LRW-RN2903") (pin "2") (pinfunction "UART_RTS_2") (pintype "output"))
    )
  )
)
